# USB-C_Messdaten.net
KiCad netlist of a schematic drawn in Altium Designer
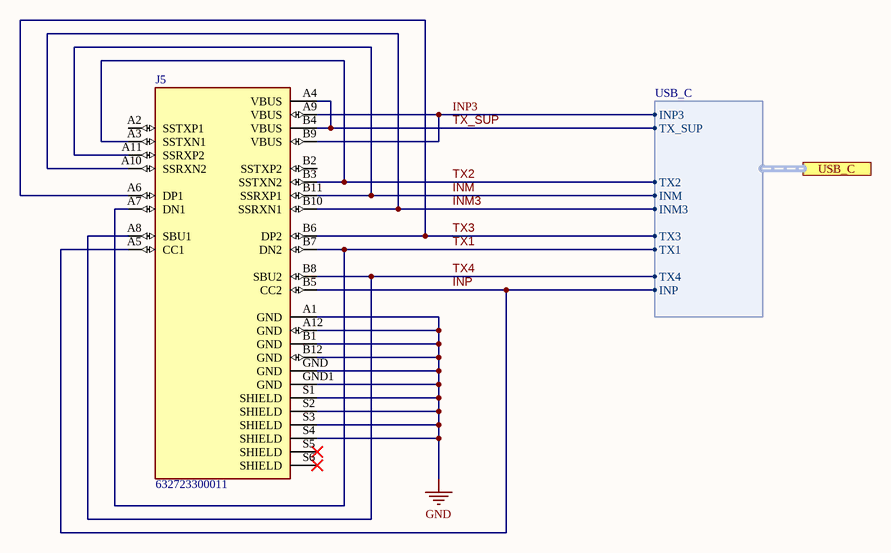
[diagram p0: USB-C_Messdaten.SchDoc]

(export (version "E")
  (design (tool "Eeschema 10.0.6"))
  (components
    (comp (ref "J5")
      (value "632723300011")
      (footprint "WURTH_632723X00011")
      (fields (field (name "MF") "Wurth Elektronik"))
      (libsource (lib "632723300011") (part "632723300011"))
    )
  )
  (nets
    (net (code "2") (name "/INM") (class "Default")
      (node (ref "J5") (pin "A11") (pinfunction "SSRXP2_A11") (pintype "bidirectional"))
      (node (ref "J5") (pin "B11") (pinfunction "SSRXP1_B11") (pintype "bidirectional"))
    )
    (net (code "3") (name "/INM3") (class "Default")
      (node (ref "J5") (pin "A10") (pinfunction "SSRXN2_A10") (pintype "bidirectional"))
      (node (ref "J5") (pin "B10") (pinfunction "SSRXN1_B10") (pintype "bidirectional"))
    )
    (net (code "4") (name "/INP") (class "Default")
      (node (ref "J5") (pin "A5") (pinfunction "CC1_A5") (pintype "bidirectional"))
      (node (ref "J5") (pin "B5") (pinfunction "CC2_B5") (pintype "bidirectional"))
    )
    (net (code "5") (name "/INP3") (class "Default")
      (node (ref "J5") (pin "A9") (pinfunction "VBUS_A9") (pintype "bidirectional"))
      (node (ref "J5") (pin "B9") (pinfunction "VBUS_B9") (pintype "bidirectional"))
    )
    (net (code "6") (name "/TX1") (class "Default")
      (node (ref "J5") (pin "A7") (pinfunction "DN1_A7") (pintype "bidirectional"))
      (node (ref "J5") (pin "B7") (pinfunction "DN2_B7") (pintype "bidirectional"))
    )
    (net (code "7") (name "/TX2") (class "Default")
      (node (ref "J5") (pin "A3") (pinfunction "SSTXN1_A3") (pintype "bidirectional"))
      (node (ref "J5") (pin "B3") (pinfunction "SSTXN2_B3") (pintype "bidirectional"))
    )
    (net (code "8") (name "/TX3") (class "Default")
      (node (ref "J5") (pin "A6") (pinfunction "DP1_A6") (pintype "bidirectional"))
      (node (ref "J5") (pin "B6") (pinfunction "DP2_B6") (pintype "bidirectional"))
    )
    (net (code "9") (name "/TX4") (class "Default")
      (node (ref "J5") (pin "A8") (pinfunction "SBU1_A8") (pintype "bidirectional"))
      (node (ref "J5") (pin "B8") (pinfunction "SBU2_B8") (pintype "bidirectional"))
    )
    (net (code "10") (name "/TX_SUP") (class "Default")
      (node (ref "J5") (pin "A4") (pinfunction "VBUS_A4") (pintype "power_in"))
      (node (ref "J5") (pin "B4") (pinfunction "VBUS_B4") (pintype "power_in"))
    )
    (net (code "12") (name "GND") (class "Default")
      (node (ref "J5") (pin "A1") (pinfunction "GND_A1") (pintype "power_in"))
      (node (ref "J5") (pin "A12") (pinfunction "GND_A12") (pintype "bidirectional"))
      (node (ref "J5") (pin "B1") (pinfunction "GND_B1") (pintype "power_in"))
      (node (ref "J5") (pin "B12") (pinfunction "GND_B12") (pintype "bidirectional"))
      (node (ref "J5") (pin "GND") (pinfunction "GND_GND") (pintype "power_in"))
      (node (ref "J5") (pin "GND1") (pinfunction "GND_GND1") (pintype "power_in"))
      (node (ref "J5") (pin "S1") (pinfunction "SHIELD_S1") (pintype "power_in"))
      (node (ref "J5") (pin "S2") (pinfunction "SHIELD_S2") (pintype "power_in"))
      (node (ref "J5") (pin "S3") (pinfunction "SHIELD_S3") (pintype "power_in"))
      (node (ref "J5") (pin "S4") (pinfunction "SHIELD_S4") (pintype "power_in"))
    )
    (net (code "13") (name "unconnected-(J5-SHIELD-PadS5)") (class "Default")
      (node (ref "J5") (pin "S5") (pinfunction "SHIELD_S5") (pintype "power_in+no_connect"))
    )
    (net (code "14") (name "unconnected-(J5-SHIELD-PadS6)") (class "Default")
      (node (ref "J5") (pin "S6") (pinfunction "SHIELD_S6") (pintype "power_in+no_connect"))
    )
    (net (code "15") (name "unconnected-(J5-SSTXP1-PadA2)") (class "Default")
      (node (ref "J5") (pin "A2") (pinfunction "SSTXP1_A2") (pintype "bidirectional"))
    )
    (net (code "16") (name "unconnected-(J5-SSTXP2-PadB2)") (class "Default")
      (node (ref "J5") (pin "B2") (pinfunction "SSTXP2_B2") (pintype "bidirectional"))
    )
  )
)
